# VREG_RT9166-12PVL.net
KiCad netlist of a schematic drawn in Altium Designer
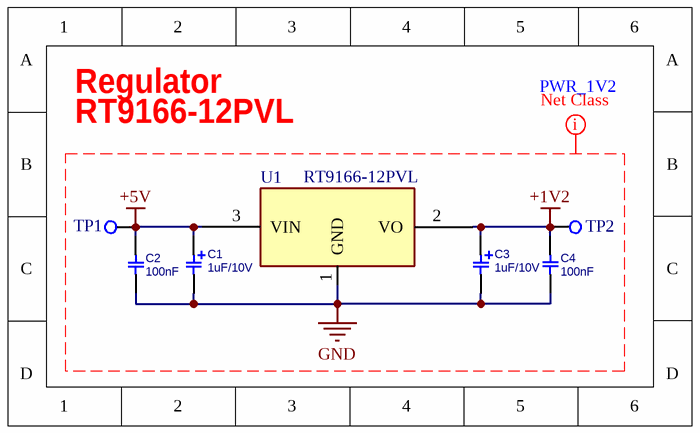
[diagram p0: VREG RT9166-12PVL.SchDoc]

(export (version "E")
  (design (tool "Eeschema 10.0.6"))
  (components
    (comp (ref "C1")
      (value "1uF/10V")
      (footprint "C_TN_A")
      (description "CAP, SMD, TAN")
      (libsource (lib "PW Components 97_492") (part "CAP_SMD_TAN"))
    )
    (comp (ref "C2")
      (value "100nF")
      (footprint "C0603S")
      (description "CAP, SMD, MLCC")
      (fields (field (name "MANF_P#") "MANF_PART#") (field (name "MANF") "Murata"))
      (libsource (lib "Passive") (part "CAP_SMD_MLCC"))
    )
    (comp (ref "C3")
      (value "1uF/10V")
      (footprint "C_TN_A")
      (description "CAP, SMD, TAN")
      (libsource (lib "PW Components 97_492") (part "CAP_SMD_TAN"))
    )
    (comp (ref "C4")
      (value "100nF")
      (footprint "C0603S")
      (description "CAP, SMD, MLCC")
      (fields (field (name "MANF_P#") "MANF_PART#") (field (name "MANF") "Murata"))
      (libsource (lib "Passive") (part "CAP_SMD_MLCC"))
    )
    (comp (ref "TP1")
      (value "Test Point")
      (footprint "TPSMD_C1")
      (libsource (lib "Passives") (part "Test Point"))
    )
    (comp (ref "TP2")
      (value "Test Point")
      (footprint "TPSMD_C1")
      (libsource (lib "Passives") (part "Test Point"))
    )
    (comp (ref "U1")
      (value "RT9166-12PVL")
      (footprint "SOT23_3")
      (description "REG, Linear, Fixed, 1.2v, 0.3A/0.6A, SOT23")
      (fields (field (name "MANF") "TI"))
      (libsource (lib "PW Components 97_481") (part "VREG_RT9166A-12PVL_SOT23"))
    )
  )
  (nets
    (net (code "1") (name "+1V2") (class "Default")
      (node (ref "C3") (pin "1") (pinfunction "1_1") (pintype "passive"))
      (node (ref "C4") (pin "1") (pinfunction "1_1") (pintype "passive"))
      (node (ref "TP2") (pin "1") (pinfunction "TP_1") (pintype "passive"))
      (node (ref "U1") (pin "2") (pinfunction "VO_2") (pintype "passive"))
    )
    (net (code "2") (name "+5V") (class "Default")
      (node (ref "C1") (pin "1") (pinfunction "1_1") (pintype "passive"))
      (node (ref "C2") (pin "1") (pinfunction "1_1") (pintype "passive"))
      (node (ref "TP1") (pin "1") (pinfunction "TP_1") (pintype "passive"))
      (node (ref "U1") (pin "3") (pinfunction "VIN_3") (pintype "passive"))
    )
    (net (code "3") (name "GND") (class "Default")
      (node (ref "C1") (pin "2") (pinfunction "2_2") (pintype "passive"))
      (node (ref "C2") (pin "2") (pinfunction "2_2") (pintype "passive"))
      (node (ref "C3") (pin "2") (pinfunction "2_2") (pintype "passive"))
      (node (ref "C4") (pin "2") (pinfunction "2_2") (pintype "passive"))
      (node (ref "U1") (pin "1") (pinfunction "GND_1") (pintype "passive"))
    )
  )
)
